# 02_USB_Bridge.net
KiCad netlist of a schematic drawn in Altium Designer
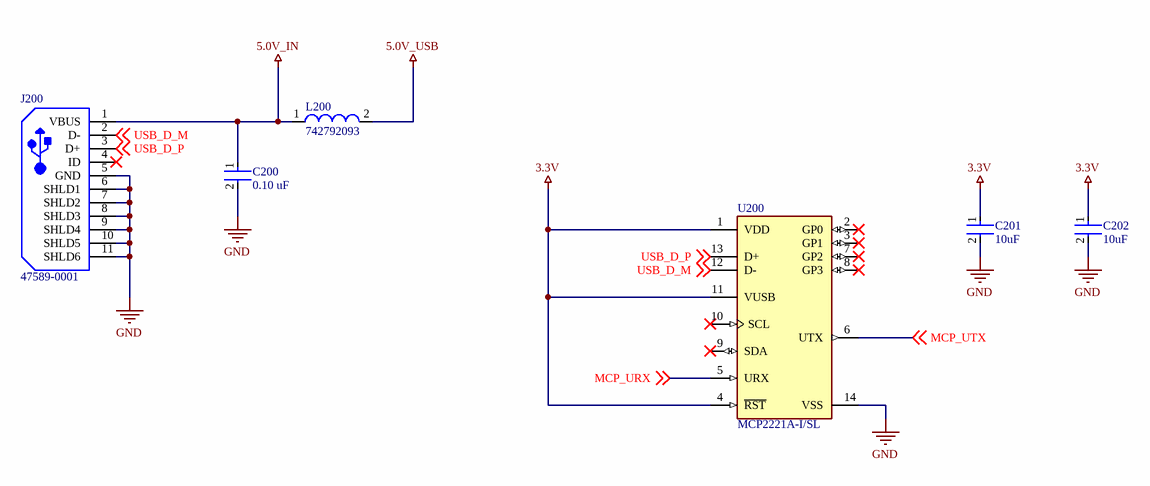
[diagram p0: 02_USB_Bridge.SchDoc]

(export (version "E")
  (design (tool "Eeschema 10.0.6"))
  (components
    (comp (ref "C200")
      (value "0.10 uF")
      (footprint "FP-C0805C-DN-MFG")
      (description "CAP CER 0.1UF 50V X7R 0805")
      (fields
        (field (name "MANUFACTURER PART NUMBER") "C0805C104K5RACTU")
        (field (name "MANUFACTURER") "KEMET")
      )
      (libsource (lib "Altium Content Vault") (part "b4654b650e69147ec39a6b967a45e02"))
    )
    (comp (ref "C201")
      (value "10uF")
      (footprint "FP-C0805C-DG-MFG")
      (description "CAP CER 10UF 10V X5R 0805")
      (fields (field (name "TOLERANCE") "10%") (field (name "MANUFACTURER PART NUMBER") "C0805C106K8PACTU"))
      (libsource (lib "Altium Content Vault") (part "11868f565c42a9108669ba33697ecf6"))
    )
    (comp (ref "C202")
      (value "10uF")
      (footprint "FP-C0805C-DG-MFG")
      (description "CAP CER 10UF 10V X5R 0805")
      (fields (field (name "TOLERANCE") "10%") (field (name "MANUFACTURER PART NUMBER") "C0805C106K8PACTU"))
      (libsource (lib "Altium Content Vault") (part "11868f565c42a9108669ba33697ecf6"))
    )
    (comp (ref "J200")
      (value "47589-0001")
      (footprint "MOLX-47589-0001_V")
      (description "Right Angle Female Type AB Micro USB Connector, 30 V, 1.8 A, -30 to 85 degC, RoHS, Tape and Reel")
      (fields (field (name "MANUFACTURER") "Molex"))
      (libsource (lib "Altium Content Vault") (part "USB-5-6SHLD"))
    )
    (comp (ref "L200")
      (value "742792093")
      (footprint "SMD-0805")
      (description "SMD EMI Suppression Ferrite Bead WE-CBF, Z = 2200 Ohm")
      (libsource (lib "Altium Content Vault") (part "PAS-IND-INDUCTOR-2"))
    )
    (comp (ref "U200")
      (value "MCP2221A-I/SL")
      (footprint "FP-C04-065-SL-MFG")
      (description "IC USB TO I2C/UART 14SOIC")
      (fields
        (field (name "OCTOPART") "https://octopart.com/mcp2221a-i%2Fsl-microchip-71704986")
        (field (name "MANUFACTURER") "Microchip")
      )
      (libsource (lib "Altium Content Vault") (part "1b53208594fde27bd45fc2fa1d78706"))
    )
  )
  (nets
    (net (code "1") (name "3.3V") (class "Default")
      (node (ref "C201") (pin "1") (pinfunction "1_1") (pintype "passive"))
      (node (ref "C202") (pin "1") (pinfunction "1_1") (pintype "passive"))
      (node (ref "U200") (pin "1") (pinfunction "VDD_1") (pintype "power_in"))
      (node (ref "U200") (pin "11") (pinfunction "VUSB_11") (pintype "power_in"))
      (node (ref "U200") (pin "4") (pinfunction "~{RST}_4") (pintype "input"))
    )
    (net (code "2") (name "5.0V_IN") (class "Default")
      (node (ref "C200") (pin "1") (pinfunction "1_1") (pintype "passive"))
      (node (ref "J200") (pin "1") (pinfunction "VBUS_1") (pintype "passive"))
      (node (ref "L200") (pin "1") (pinfunction "1_1") (pintype "passive"))
    )
    (net (code "3") (name "5.0V_USB") (class "Default")
      (node (ref "L200") (pin "2") (pinfunction "2_2") (pintype "passive"))
    )
    (net (code "4") (name "GND") (class "Default")
      (node (ref "C200") (pin "2") (pinfunction "2_2") (pintype "passive"))
      (node (ref "C201") (pin "2") (pinfunction "2_2") (pintype "passive"))
      (node (ref "C202") (pin "2") (pinfunction "2_2") (pintype "passive"))
      (node (ref "J200") (pin "10") (pinfunction "SHLD5_10") (pintype "passive"))
      (node (ref "J200") (pin "11") (pinfunction "SHLD6_11") (pintype "passive"))
      (node (ref "J200") (pin "5") (pinfunction "GND_5") (pintype "passive"))
      (node (ref "J200") (pin "6") (pinfunction "SHLD1_6") (pintype "passive"))
      (node (ref "J200") (pin "7") (pinfunction "SHLD2_7") (pintype "passive"))
      (node (ref "J200") (pin "8") (pinfunction "SHLD3_8") (pintype "passive"))
      (node (ref "J200") (pin "9") (pinfunction "SHLD4_9") (pintype "passive"))
      (node (ref "U200") (pin "14") (pinfunction "VSS_14") (pintype "power_in"))
    )
    (net (code "5") (name "MCP_URX") (class "Default")
      (node (ref "U200") (pin "5") (pinfunction "URX_5") (pintype "input"))
    )
    (net (code "6") (name "MCP_UTX") (class "Default")
      (node (ref "U200") (pin "6") (pinfunction "UTX_6") (pintype "output"))
    )
    (net (code "7") (name "USB_D_M") (class "Default")
      (node (ref "J200") (pin "2") (pinfunction "D-_2") (pintype "passive"))
      (node (ref "U200") (pin "12") (pinfunction "D-_12") (pintype "power_in"))
    )
    (net (code "8") (name "USB_D_P") (class "Default")
      (node (ref "J200") (pin "3") (pinfunction "D+_3") (pintype "passive"))
      (node (ref "U200") (pin "13") (pinfunction "D+_13") (pintype "power_in"))
    )
    (net (code "9") (name "unconnected-(J200-ID-Pad4)") (class "Default")
      (node (ref "J200") (pin "4") (pinfunction "ID_4") (pintype "passive+no_connect"))
    )
    (net (code "10") (name "unconnected-(U200-GP0-Pad2)") (class "Default")
      (node (ref "U200") (pin "2") (pinfunction "GP0_2") (pintype "bidirectional+no_connect"))
    )
    (net (code "11") (name "unconnected-(U200-GP1-Pad3)") (class "Default")
      (node (ref "U200") (pin "3") (pinfunction "GP1_3") (pintype "bidirectional+no_connect"))
    )
    (net (code "12") (name "unconnected-(U200-GP2-Pad7)") (class "Default")
      (node (ref "U200") (pin "7") (pinfunction "GP2_7") (pintype "bidirectional+no_connect"))
    )
    (net (code "13") (name "unconnected-(U200-GP3-Pad8)") (class "Default")
      (node (ref "U200") (pin "8") (pinfunction "GP3_8") (pintype "bidirectional+no_connect"))
    )
    (net (code "14") (name "unconnected-(U200-SCL-Pad10)") (class "Default")
      (node (ref "U200") (pin "10") (pinfunction "SCL_10") (pintype "input+no_connect"))
    )
    (net (code "15") (name "unconnected-(U200-SDA-Pad9)") (class "Default")
      (node (ref "U200") (pin "9") (pinfunction "SDA_9") (pintype "bidirectional+no_connect"))
    )
  )
)
